# DriverBoard.net
KiCad netlist of a schematic drawn in Altium Designer
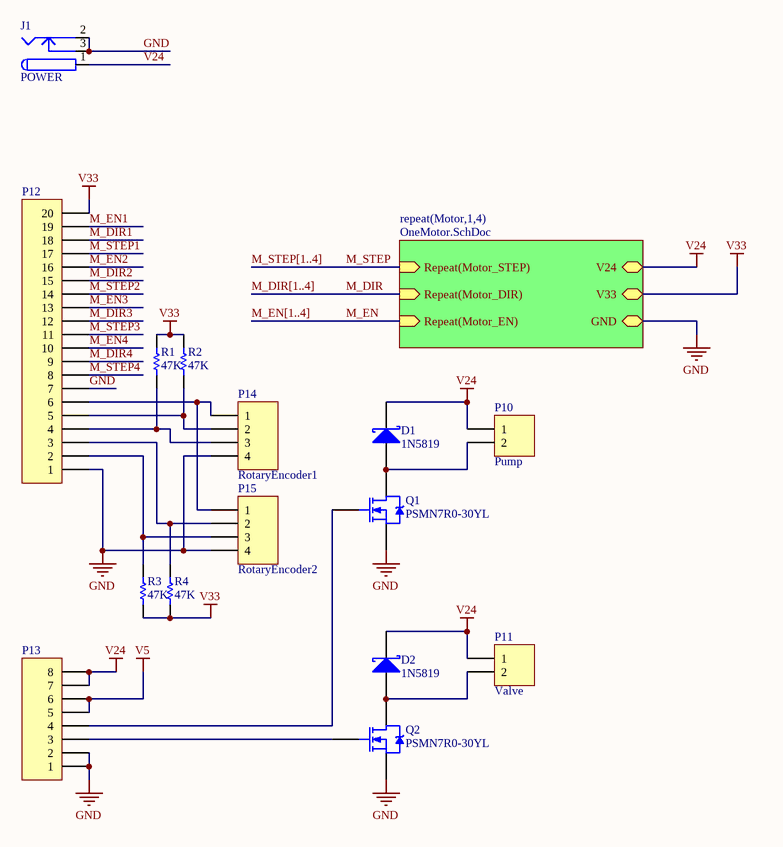
[diagram p0: DriverBoard.SchDoc]

(export (version "E")
  (design (tool "Eeschema 10.0.6"))
  (components
    (comp (ref "D1")
      (value "1N5819")
      (footprint "DO-214AC")
      (description "Schottky Diode")
      (fields (field (name "PUBLISHER") "Altium Limited"))
      (libsource (lib "Miscellaneous Devices") (part "D Schottky"))
    )
    (comp (ref "D2")
      (value "1N5819")
      (footprint "DO-214AC")
      (description "Schottky Diode")
      (fields (field (name "PUBLISHER") "Altium Limited"))
      (libsource (lib "Miscellaneous Devices") (part "D Schottky"))
    )
    (comp (ref "J1") (value "POWER") (footprint "DC_POWER") (libsource (lib "Schlib1") (part "POWER2.5")))
    (comp (ref "P10")
      (value "Pump")
      (footprint "HDR1X2H")
      (description "Header, 2-Pin, Right Angle")
      (fields (field (name "PUBLISHER") "Altium Limited"))
      (libsource (lib "Miscellaneous Connectors") (part "Header 2H"))
    )
    (comp (ref "P11")
      (value "Valve")
      (footprint "HDR1X2H")
      (description "Header, 2-Pin, Right Angle")
      (fields (field (name "PUBLISHER") "Altium Limited"))
      (libsource (lib "Miscellaneous Connectors") (part "Header 2H"))
    )
    (comp (ref "P12")
      (value "Header 20")
      (footprint "HDR1X20")
      (description "Header, 20-Pin")
      (fields (field (name "PUBLISHER") "Altium Limited"))
      (libsource (lib "Miscellaneous Connectors") (part "Header 20"))
    )
    (comp (ref "P13")
      (value "Header 8")
      (footprint "HDR1X8")
      (description "Header, 8-Pin")
      (fields (field (name "PUBLISHER") "Altium Limited"))
      (libsource (lib "Miscellaneous Connectors") (part "Header 8"))
    )
    (comp (ref "P14")
      (value "RotaryEncoder1")
      (footprint "HDR1X4H")
      (description "Header, 4-Pin, Right Angle")
      (fields (field (name "PUBLISHER") "Altium Limited"))
      (libsource (lib "Miscellaneous Connectors") (part "Header 4H"))
    )
    (comp (ref "P15")
      (value "RotaryEncoder2")
      (footprint "HDR1X4H")
      (description "Header, 4-Pin, Right Angle")
      (fields (field (name "PUBLISHER") "Altium Limited"))
      (libsource (lib "Miscellaneous Connectors") (part "Header 4H"))
    )
    (comp (ref "Q1")
      (value "PSMN7R0-30YL")
      (footprint "SOT669")
      (description "N-Channel Power MOSFET")
      (fields (field (name "PUBLISHER") "Altium Limited"))
      (libsource (lib "Miscellaneous Devices") (part "NMOS-2"))
    )
    (comp (ref "Q2")
      (value "PSMN7R0-30YL")
      (footprint "SOT669")
      (description "N-Channel Power MOSFET")
      (fields (field (name "PUBLISHER") "Altium Limited"))
      (libsource (lib "Miscellaneous Devices") (part "NMOS-2"))
    )
    (comp (ref "R1")
      (value "47K")
      (footprint "R-1608[0603]")
      (description "Semiconductor Resistor")
      (fields (field (name "Comment") "Res Semi") (field (name "PUBLISHER") "Altium Limited"))
      (libsource (lib "Miscellaneous Devices") (part "Res Semi"))
    )
    (comp (ref "R2")
      (value "47K")
      (footprint "R-1608[0603]")
      (description "Semiconductor Resistor")
      (fields (field (name "Comment") "Res Semi") (field (name "PUBLISHER") "Altium Limited"))
      (libsource (lib "Miscellaneous Devices") (part "Res Semi"))
    )
    (comp (ref "R3")
      (value "47K")
      (footprint "R-1608[0603]")
      (description "Semiconductor Resistor")
      (fields (field (name "Comment") "Res Semi") (field (name "PUBLISHER") "Altium Limited"))
      (libsource (lib "Miscellaneous Devices") (part "Res Semi"))
    )
    (comp (ref "R4")
      (value "47K")
      (footprint "R-1608[0603]")
      (description "Semiconductor Resistor")
      (fields (field (name "Comment") "Res Semi") (field (name "PUBLISHER") "Altium Limited"))
      (libsource (lib "Miscellaneous Devices") (part "Res Semi"))
    )
  )
  (nets
    (net (code "2") (name "/M_DIR1") (class "Default")
      (node (ref "P12") (pin "18") (pinfunction "18_18") (pintype "passive"))
    )
    (net (code "3") (name "/M_DIR2") (class "Default")
      (node (ref "P12") (pin "15") (pinfunction "15_15") (pintype "passive"))
    )
    (net (code "4") (name "/M_DIR3") (class "Default")
      (node (ref "P12") (pin "12") (pinfunction "12_12") (pintype "passive"))
    )
    (net (code "5") (name "/M_DIR4") (class "Default")
      (node (ref "P12") (pin "9") (pinfunction "9_9") (pintype "passive"))
    )
    (net (code "8") (name "/M_EN1") (class "Default")
      (node (ref "P12") (pin "19") (pinfunction "19_19") (pintype "passive"))
    )
    (net (code "9") (name "/M_EN2") (class "Default")
      (node (ref "P12") (pin "16") (pinfunction "16_16") (pintype "passive"))
    )
    (net (code "10") (name "/M_EN3") (class "Default")
      (node (ref "P12") (pin "13") (pinfunction "13_13") (pintype "passive"))
    )
    (net (code "11") (name "/M_EN4") (class "Default")
      (node (ref "P12") (pin "10") (pinfunction "10_10") (pintype "passive"))
    )
    (net (code "14") (name "/M_STEP1") (class "Default")
      (node (ref "P12") (pin "17") (pinfunction "17_17") (pintype "passive"))
    )
    (net (code "15") (name "/M_STEP2") (class "Default")
      (node (ref "P12") (pin "14") (pinfunction "14_14") (pintype "passive"))
    )
    (net (code "16") (name "/M_STEP3") (class "Default")
      (node (ref "P12") (pin "11") (pinfunction "11_11") (pintype "passive"))
    )
    (net (code "17") (name "/M_STEP4") (class "Default")
      (node (ref "P12") (pin "8") (pinfunction "8_8") (pintype "passive"))
    )
    (net (code "19") (name "GND") (class "Default")
      (node (ref "J1") (pin "2") (pintype "passive"))
      (node (ref "J1") (pin "3") (pintype "passive"))
      (node (ref "P12") (pin "1") (pinfunction "1_1") (pintype "passive"))
      (node (ref "P12") (pin "7") (pinfunction "7_7") (pintype "passive"))
      (node (ref "P13") (pin "1") (pinfunction "1_1") (pintype "passive"))
      (node (ref "P13") (pin "2") (pinfunction "2_2") (pintype "passive"))
      (node (ref "P14") (pin "4") (pinfunction "4_4") (pintype "passive"))
      (node (ref "P15") (pin "4") (pinfunction "4_4") (pintype "passive"))
      (node (ref "Q1") (pin "3") (pinfunction "S_3") (pintype "passive"))
      (node (ref "Q2") (pin "3") (pinfunction "S_3") (pintype "passive"))
    )
    (net (code "20") (name "Net-(D1-A)") (class "Default")
      (node (ref "D1") (pin "1") (pinfunction "A_1") (pintype "passive"))
      (node (ref "P10") (pin "2") (pinfunction "2_2") (pintype "passive"))
      (node (ref "Q1") (pin "2") (pinfunction "D_2") (pintype "passive"))
    )
    (net (code "21") (name "Net-(D2-A)") (class "Default")
      (node (ref "D2") (pin "1") (pinfunction "A_1") (pintype "passive"))
      (node (ref "P11") (pin "2") (pinfunction "2_2") (pintype "passive"))
      (node (ref "Q2") (pin "2") (pinfunction "D_2") (pintype "passive"))
    )
    (net (code "22") (name "Net-(P12-Pad2)") (class "Default")
      (node (ref "P12") (pin "2") (pinfunction "2_2") (pintype "passive"))
      (node (ref "P15") (pin "3") (pinfunction "3_3") (pintype "passive"))
      (node (ref "R3") (pin "2") (pinfunction "2_2") (pintype "passive"))
    )
    (net (code "23") (name "Net-(P12-Pad3)") (class "Default")
      (node (ref "P12") (pin "3") (pinfunction "3_3") (pintype "passive"))
      (node (ref "P15") (pin "2") (pinfunction "2_2") (pintype "passive"))
      (node (ref "R4") (pin "2") (pinfunction "2_2") (pintype "passive"))
    )
    (net (code "24") (name "Net-(P12-Pad4)") (class "Default")
      (node (ref "P12") (pin "4") (pinfunction "4_4") (pintype "passive"))
      (node (ref "P14") (pin "3") (pinfunction "3_3") (pintype "passive"))
      (node (ref "R1") (pin "1") (pinfunction "1_1") (pintype "passive"))
    )
    (net (code "25") (name "Net-(P12-Pad5)") (class "Default")
      (node (ref "P12") (pin "5") (pinfunction "5_5") (pintype "passive"))
      (node (ref "P14") (pin "2") (pinfunction "2_2") (pintype "passive"))
      (node (ref "R2") (pin "1") (pinfunction "1_1") (pintype "passive"))
    )
    (net (code "26") (name "Net-(P12-Pad6)") (class "Default")
      (node (ref "P12") (pin "6") (pinfunction "6_6") (pintype "passive"))
      (node (ref "P14") (pin "1") (pinfunction "1_1") (pintype "passive"))
      (node (ref "P15") (pin "1") (pinfunction "1_1") (pintype "passive"))
    )
    (net (code "27") (name "Net-(Q1-G)") (class "Default")
      (node (ref "P13") (pin "4") (pinfunction "4_4") (pintype "passive"))
      (node (ref "Q1") (pin "1") (pinfunction "G_1") (pintype "passive"))
    )
    (net (code "28") (name "Net-(Q2-G)") (class "Default")
      (node (ref "P13") (pin "3") (pinfunction "3_3") (pintype "passive"))
      (node (ref "Q2") (pin "1") (pinfunction "G_1") (pintype "passive"))
    )
    (net (code "29") (name "V5") (class "Default")
      (node (ref "P13") (pin "5") (pinfunction "5_5") (pintype "passive"))
      (node (ref "P13") (pin "6") (pinfunction "6_6") (pintype "passive"))
    )
    (net (code "30") (name "V24") (class "Default")
      (node (ref "D1") (pin "2") (pinfunction "K_2") (pintype "passive"))
      (node (ref "D2") (pin "2") (pinfunction "K_2") (pintype "passive"))
      (node (ref "J1") (pin "1") (pintype "passive"))
      (node (ref "P10") (pin "1") (pinfunction "1_1") (pintype "passive"))
      (node (ref "P11") (pin "1") (pinfunction "1_1") (pintype "passive"))
      (node (ref "P13") (pin "7") (pinfunction "7_7") (pintype "passive"))
      (node (ref "P13") (pin "8") (pinfunction "8_8") (pintype "passive"))
    )
    (net (code "31") (name "V33") (class "Default")
      (node (ref "P12") (pin "20") (pinfunction "20_20") (pintype "passive"))
      (node (ref "R1") (pin "2") (pinfunction "2_2") (pintype "passive"))
      (node (ref "R2") (pin "2") (pinfunction "2_2") (pintype "passive"))
      (node (ref "R3") (pin "1") (pinfunction "1_1") (pintype "passive"))
      (node (ref "R4") (pin "1") (pinfunction "1_1") (pintype "passive"))
    )
  )
)
